# SCH_Namu_Board_v1_2023-11-06.net
KiCad netlist of a schematic drawn in EasyEDA
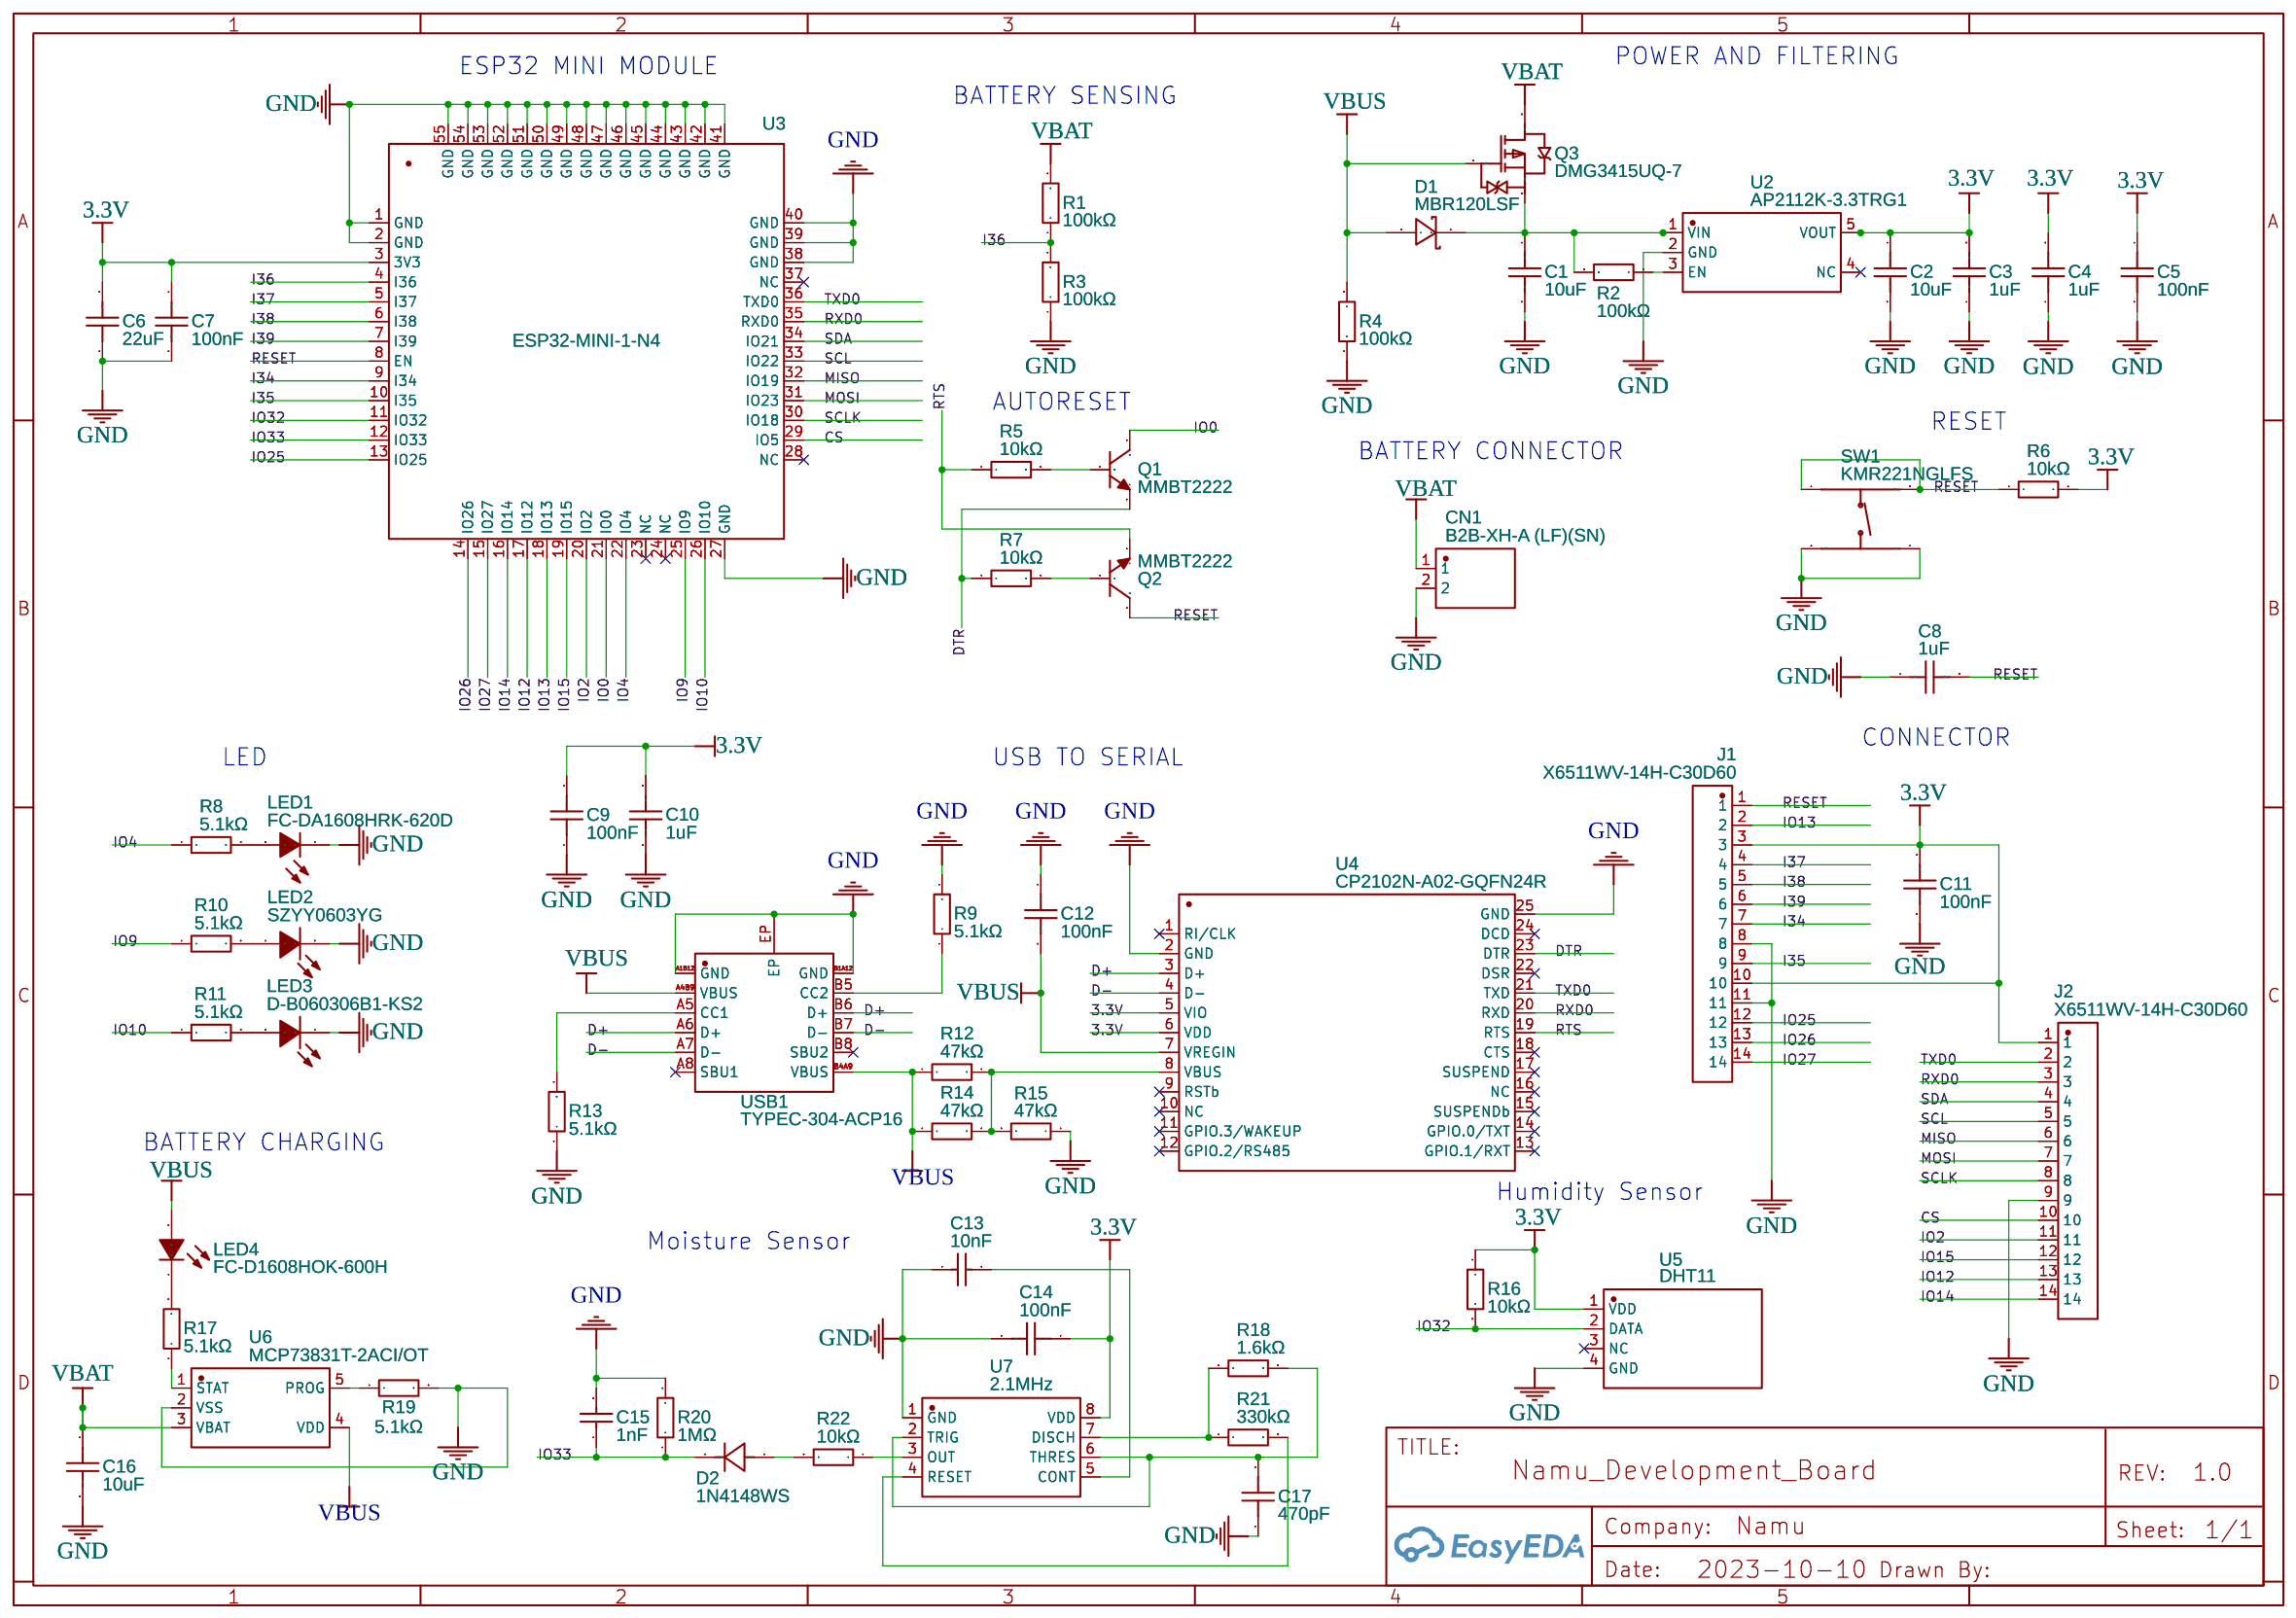
[diagram p0: schematic sheet]

(export (version "E")
  (design (tool "Eeschema 10.0.6"))
  (components
    (comp (ref "C1")
      (value "10uF")
      (fields
        (field (name "Manufacturer Part") "CS3216X7R106K250NRI")
        (field (name "Manufacturer") "SAMWHA(三和)")
      )
      (libsource (lib "") (part "CS3216X7R106K250NRI"))
    )
    (comp (ref "C2")
      (value "10uF")
      (fields
        (field (name "Manufacturer Part") "CS3216X7R106K250NRI")
        (field (name "Manufacturer") "SAMWHA(三和)")
      )
      (libsource (lib "") (part "CS3216X7R106K250NRI"))
    )
    (comp (ref "C3")
      (value "1uF")
      (fields
        (field (name "Manufacturer Part") "CS1608X7R105K250NRB")
        (field (name "Manufacturer") "SAMWHA(三和)")
      )
      (libsource (lib "") (part "CS1608X7R105K250NRB_1"))
    )
    (comp (ref "C4")
      (value "1uF")
      (fields
        (field (name "Manufacturer Part") "CS1608X7R105K250NRB")
        (field (name "Manufacturer") "SAMWHA(三和)")
      )
      (libsource (lib "") (part "CS1608X7R105K250NRB_1"))
    )
    (comp (ref "C5")
      (value "100nF")
      (fields (field (name "Manufacturer Part") "C1005X5R1C104KT000F") (field (name "Manufacturer") "TDK"))
      (libsource (lib "") (part "C1005X5R1C104KT000F"))
    )
    (comp (ref "C6")
      (value "22uF")
      (fields
        (field (name "Manufacturer Part") "CS3216X5R226K160NRI")
        (field (name "Manufacturer") "SAMWHA(三和)")
      )
      (libsource (lib "") (part "CS3216X5R226K160NRI"))
    )
    (comp (ref "C7")
      (value "100nF")
      (fields (field (name "Manufacturer Part") "C1005X5R1C104KT000F") (field (name "Manufacturer") "TDK"))
      (libsource (lib "") (part "C1005X5R1C104KT000F"))
    )
    (comp (ref "C8")
      (value "1uF")
      (fields
        (field (name "Manufacturer Part") "CS1608X7R105K250NRB")
        (field (name "Manufacturer") "SAMWHA(三和)")
      )
      (libsource (lib "") (part "CS1608X7R105K250NRB"))
    )
    (comp (ref "C9")
      (value "100nF")
      (fields (field (name "Manufacturer Part") "C1005X5R1C104KT000F") (field (name "Manufacturer") "TDK"))
      (libsource (lib "") (part "C1005X5R1C104KT000F_2"))
    )
    (comp (ref "C10")
      (value "1uF")
      (fields
        (field (name "Manufacturer Part") "CS1608X7R105K250NRB")
        (field (name "Manufacturer") "SAMWHA(三和)")
      )
      (libsource (lib "") (part "CS1608X7R105K250NRB_1"))
    )
    (comp (ref "C11")
      (value "100nF")
      (fields (field (name "Manufacturer Part") "C1005X5R1C104KT000F") (field (name "Manufacturer") "TDK"))
      (libsource (lib "") (part "C1005X5R1C104KT000F"))
    )
    (comp (ref "C12")
      (value "100nF")
      (fields (field (name "Manufacturer Part") "C1005X5R1C104KT000F") (field (name "Manufacturer") "TDK"))
      (libsource (lib "") (part "C1005X5R1C104KT000F"))
    )
    (comp (ref "C13")
      (value "10nF")
      (fields
        (field (name "Manufacturer Part") "CC0402KRX7R9BB103")
        (field (name "Manufacturer") "YAGEO(国巨)")
      )
      (libsource (lib "") (part "CC0402KRX7R9BB103"))
    )
    (comp (ref "C14")
      (value "100nF")
      (fields (field (name "Manufacturer Part") "C1005X5R1C104KT000F") (field (name "Manufacturer") "TDK"))
      (libsource (lib "") (part "C1005X5R1C104KT000F_1"))
    )
    (comp (ref "C15")
      (value "1nF")
      (fields
        (field (name "Manufacturer Part") "CC0402KRX7R9BB102")
        (field (name "Manufacturer") "YAGEO(国巨)")
      )
      (libsource (lib "") (part "CC0402KRX7R9BB102"))
    )
    (comp (ref "C16")
      (value "10uF")
      (fields
        (field (name "Manufacturer Part") "CS3216X7R106K250NRI")
        (field (name "Manufacturer") "SAMWHA(三和)")
      )
      (libsource (lib "") (part "CS3216X7R106K250NRI"))
    )
    (comp (ref "C17")
      (value "470pF")
      (fields
        (field (name "Manufacturer Part") "CC0402KRX7R9BB471")
        (field (name "Manufacturer") "YAGEO(国巨)")
      )
      (libsource (lib "") (part "CC0402KRX7R9BB471"))
    )
    (comp (ref "CN1")
      (value "B2B-XH-A (LF)(SN)")
      (fields (field (name "Manufacturer Part") "B2B-XH-A(LF)(SN)") (field (name "Manufacturer") "JST"))
      (libsource (lib "") (part "B2B-XH-A (LF)(SN)"))
    )
    (comp (ref "D1")
      (value "MBR120LSF")
      (fields (field (name "Manufacturer") "SHIKUES(时科)"))
      (libsource (lib "") (part "MBR120LSF"))
    )
    (comp (ref "D2")
      (value "1N4148WS")
      (fields (field (name "Manufacturer") "TWGMC(台湾迪嘉)"))
      (libsource (lib "") (part "1N4148WS_C727111"))
    )
    (comp (ref "J1")
      (value "X6511WV-14H-C30D60")
      (fields (field (name "Manufacturer") "XKB Connectivity(中国星坤)"))
      (libsource (lib "") (part "X6511WV-14H-C30D60"))
    )
    (comp (ref "J2")
      (value "X6511WV-14H-C30D60")
      (fields (field (name "Manufacturer") "XKB Connectivity(中国星坤)"))
      (libsource (lib "") (part "X6511WV-14H-C30D60_1"))
    )
    (comp (ref "LED1")
      (value "FC-DA1608HRK-620D")
      (fields (field (name "Manufacturer Part") "NCD0603R1") (field (name "Manufacturer") "国星光电"))
      (libsource (lib "") (part "FC-DA1608HRK-620D"))
    )
    (comp (ref "LED2")
      (value "SZYY0603YG")
      (fields (field (name "Manufacturer") "yongyu(永裕光电)"))
      (libsource (lib "") (part "SZYY0603YG"))
    )
    (comp (ref "LED3")
      (value "D-B060306B1-KS2")
      (fields (field (name "Manufacturer Part") "D-060306B1") (field (name "Manufacturer") "ARKLED(方舟)"))
      (libsource (lib "") (part "D-B060306B1-KS2"))
    )
    (comp (ref "LED4")
      (value "FC-D1608HOK-600H")
      (fields (field (name "Manufacturer Part") "NCD0603O1") (field (name "Manufacturer") "国星光电"))
      (libsource (lib "") (part "FC-D1608HOK-600H"))
    )
    (comp (ref "Q1")
      (value "MMBT2222")
      (fields (field (name "Manufacturer") "YONGYUTAI(永裕泰)"))
      (libsource (lib "") (part "MMBT2222_1"))
    )
    (comp (ref "Q2")
      (value "MMBT2222")
      (fields (field (name "Manufacturer") "YONGYUTAI(永裕泰)"))
      (libsource (lib "") (part "MMBT2222"))
    )
    (comp (ref "Q3")
      (value "DMG3415UQ-7")
      (fields (field (name "Manufacturer") "DIODES(美台)"))
      (libsource (lib "") (part "DMG3415UQ-7"))
    )
    (comp (ref "R1")
      (value "100kΩ")
      (fields
        (field (name "Manufacturer Part") "0603WAF1003T5E")
        (field (name "Manufacturer") "UNI-ROYAL(厚声)")
      )
      (libsource (lib "") (part "0603WAF1003T5E_1"))
    )
    (comp (ref "R2")
      (value "100kΩ")
      (fields
        (field (name "Manufacturer Part") "0603WAF1003T5E")
        (field (name "Manufacturer") "UNI-ROYAL(厚声)")
      )
      (libsource (lib "") (part "0603WAF1003T5E"))
    )
    (comp (ref "R3")
      (value "100kΩ")
      (fields
        (field (name "Manufacturer Part") "0603WAF1003T5E")
        (field (name "Manufacturer") "UNI-ROYAL(厚声)")
      )
      (libsource (lib "") (part "0603WAF1003T5E_1"))
    )
    (comp (ref "R4")
      (value "100kΩ")
      (fields
        (field (name "Manufacturer Part") "0603WAF1003T5E")
        (field (name "Manufacturer") "UNI-ROYAL(厚声)")
      )
      (libsource (lib "") (part "0603WAF1003T5E_1"))
    )
    (comp (ref "R5")
      (value "10kΩ")
      (fields (field (name "Manufacturer Part") "RC0603FR-0710KL") (field (name "Manufacturer") "YAGEO(国巨)"))
      (libsource (lib "") (part "RC0603FR-0710KL"))
    )
    (comp (ref "R6")
      (value "10kΩ")
      (fields (field (name "Manufacturer Part") "RC0603FR-0710KL") (field (name "Manufacturer") "YAGEO(国巨)"))
      (libsource (lib "") (part "RC0603FR-0710KL"))
    )
    (comp (ref "R7")
      (value "10kΩ")
      (fields (field (name "Manufacturer Part") "RC0603FR-0710KL") (field (name "Manufacturer") "YAGEO(国巨)"))
      (libsource (lib "") (part "RC0603FR-0710KL"))
    )
    (comp (ref "R8")
      (value "5.1kΩ")
      (fields (field (name "Manufacturer Part") "RMC04025.1K5%N") (field (name "Manufacturer") "Tyohm(幸亚电阻)"))
      (libsource (lib "") (part "RMC04025.1K5%N_1"))
    )
    (comp (ref "R9")
      (value "5.1kΩ")
      (fields (field (name "Manufacturer Part") "RMC04025.1K5%N") (field (name "Manufacturer") "Tyohm(幸亚电阻)"))
      (libsource (lib "") (part "RMC04025.1K5%N"))
    )
    (comp (ref "R10")
      (value "5.1kΩ")
      (fields (field (name "Manufacturer Part") "RMC04025.1K5%N") (field (name "Manufacturer") "Tyohm(幸亚电阻)"))
      (libsource (lib "") (part "RMC04025.1K5%N_1"))
    )
    (comp (ref "R11")
      (value "5.1kΩ")
      (fields (field (name "Manufacturer Part") "RMC04025.1K5%N") (field (name "Manufacturer") "Tyohm(幸亚电阻)"))
      (libsource (lib "") (part "RMC04025.1K5%N_1"))
    )
    (comp (ref "R12")
      (value "47kΩ")
      (fields
        (field (name "Manufacturer Part") "0402WGF4702TCE")
        (field (name "Manufacturer") "UNI-ROYAL(厚声)")
      )
      (libsource (lib "") (part "0402WGF4702TCE_1"))
    )
    (comp (ref "R13")
      (value "5.1kΩ")
      (fields (field (name "Manufacturer Part") "RMC04025.1K5%N") (field (name "Manufacturer") "Tyohm(幸亚电阻)"))
      (libsource (lib "") (part "RMC04025.1K5%N"))
    )
    (comp (ref "R14")
      (value "47kΩ")
      (fields
        (field (name "Manufacturer Part") "0402WGF4702TCE")
        (field (name "Manufacturer") "UNI-ROYAL(厚声)")
      )
      (libsource (lib "") (part "0402WGF4702TCE_1"))
    )
    (comp (ref "R15")
      (value "47kΩ")
      (fields
        (field (name "Manufacturer Part") "0402WGF4702TCE")
        (field (name "Manufacturer") "UNI-ROYAL(厚声)")
      )
      (libsource (lib "") (part "0402WGF4702TCE"))
    )
    (comp (ref "R16")
      (value "10kΩ")
      (fields (field (name "Manufacturer Part") "RC0603FR-0710KL") (field (name "Manufacturer") "YAGEO(国巨)"))
      (libsource (lib "") (part "RC0603FR-0710KL_2"))
    )
    (comp (ref "R17")
      (value "5.1kΩ")
      (fields (field (name "Manufacturer Part") "RMC04025.1K5%N") (field (name "Manufacturer") "Tyohm(幸亚电阻)"))
      (libsource (lib "") (part "RMC04025.1K5%N"))
    )
    (comp (ref "R18")
      (value "1.6kΩ")
      (fields
        (field (name "Manufacturer Part") "0402WGF1601TCE")
        (field (name "Manufacturer") "UNI-ROYAL(厚声)")
      )
      (libsource (lib "") (part "0402WGF1601TCE"))
    )
    (comp (ref "R19")
      (value "5.1kΩ")
      (fields (field (name "Manufacturer Part") "RMC04025.1K5%N") (field (name "Manufacturer") "Tyohm(幸亚电阻)"))
      (libsource (lib "") (part "RMC04025.1K5%N_1"))
    )
    (comp (ref "R20")
      (value "1MΩ")
      (fields
        (field (name "Manufacturer Part") "0402WGF1004TCE")
        (field (name "Manufacturer") "UNI-ROYAL(厚声)")
      )
      (libsource (lib "") (part "0402WGF1004TCE"))
    )
    (comp (ref "R21")
      (value "330kΩ")
      (fields
        (field (name "Manufacturer Part") "0402WGF3303TCE")
        (field (name "Manufacturer") "UNI-ROYAL(厚声)")
      )
      (libsource (lib "") (part "0402WGF3303TCE"))
    )
    (comp (ref "R22")
      (value "10kΩ")
      (fields (field (name "Manufacturer Part") "RC0603FR-0710KL") (field (name "Manufacturer") "YAGEO(国巨)"))
      (libsource (lib "") (part "RC0603FR-0710KL_1"))
    )
    (comp (ref "SW1")
      (value "KMR221NGLFS")
      (fields (field (name "Manufacturer") "C&K"))
      (libsource (lib "") (part "KMR221NGLFS"))
    )
    (comp (ref "U2")
      (value "AP2112K-3.3TRG1")
      (fields (field (name "Manufacturer") "DIODES(美台)"))
      (libsource (lib "") (part "AP2112K-3.3TRG1"))
    )
    (comp (ref "U3")
      (value "ESP32-MINI-1-N4")
      (fields (field (name "Manufacturer") "ESPRESSIF(乐鑫)"))
      (libsource (lib "") (part "ESP32-MINI-1-N4"))
    )
    (comp (ref "U4")
      (value "CP2102N-A02-GQFN24R")
      (fields (field (name "Manufacturer") "SILICON LABS(芯科)"))
      (libsource (lib "") (part "CP2102N-A02-GQFN24R"))
    )
    (comp (ref "U5")
      (value "DHT11")
      (fields (field (name "Manufacturer") "广州奥松"))
      (libsource (lib "") (part "DHT11"))
    )
    (comp (ref "U6")
      (value "MCP73831T-2ACI/OT")
      (fields (field (name "Manufacturer") "MICROCHIP(美国微芯)"))
      (libsource (lib "") (part "MCP73831T-2ACI/OT"))
    )
    (comp (ref "U7")
      (value "2.1MHz")
      (fields (field (name "Manufacturer Part") "TLC555IDR") (field (name "Manufacturer") "TI(德州仪器)"))
      (libsource (lib "") (part "TLC555IDR"))
    )
    (comp (ref "USB1")
      (value "TYPEC-304-ACP16")
      (fields (field (name "Manufacturer") "XUNPU(讯普)"))
      (libsource (lib "") (part "TYPEC-304-ACP16"))
    )
  )
  (nets
    (net (code "1") (name "/CS") (class "Default")
      (node (ref "J2") (pin "10") (pinfunction "10_10") (pintype "unspecified"))
      (node (ref "U3") (pin "29") (pinfunction "IO5_29") (pintype "unspecified"))
    )
    (net (code "2") (name "/D+") (class "Default")
      (node (ref "U4") (pin "3") (pinfunction "D+_3") (pintype "unspecified"))
      (node (ref "USB1") (pin "A6") (pinfunction "D+_A6") (pintype "unspecified"))
      (node (ref "USB1") (pin "B6") (pinfunction "D+_B6") (pintype "unspecified"))
    )
    (net (code "3") (name "/D-") (class "Default")
      (node (ref "U4") (pin "4") (pinfunction "D-_4") (pintype "unspecified"))
      (node (ref "USB1") (pin "A7") (pinfunction "D-_A7") (pintype "unspecified"))
      (node (ref "USB1") (pin "B7") (pinfunction "D-_B7") (pintype "unspecified"))
    )
    (net (code "4") (name "/DTR") (class "Default")
      (node (ref "Q1") (pin "2") (pinfunction "E_2") (pintype "input"))
      (node (ref "R7") (pin "1") (pinfunction "1_1") (pintype "input"))
      (node (ref "U4") (pin "23") (pinfunction "DTR_23") (pintype "unspecified"))
    )
    (net (code "5") (name "/I34") (class "Default")
      (node (ref "J1") (pin "7") (pinfunction "7_7") (pintype "unspecified"))
      (node (ref "U3") (pin "9") (pinfunction "I34_9") (pintype "unspecified"))
    )
    (net (code "6") (name "/I35") (class "Default")
      (node (ref "J1") (pin "9") (pinfunction "9_9") (pintype "unspecified"))
      (node (ref "U3") (pin "10") (pinfunction "I35_10") (pintype "unspecified"))
    )
    (net (code "7") (name "/I36") (class "Default")
      (node (ref "R1") (pin "1") (pinfunction "1_1") (pintype "input"))
      (node (ref "R3") (pin "2") (pinfunction "2_2") (pintype "input"))
      (node (ref "U3") (pin "4") (pinfunction "I36_4") (pintype "unspecified"))
    )
    (net (code "8") (name "/I37") (class "Default")
      (node (ref "J1") (pin "4") (pinfunction "4_4") (pintype "unspecified"))
      (node (ref "U3") (pin "5") (pinfunction "I37_5") (pintype "unspecified"))
    )
    (net (code "9") (name "/I38") (class "Default")
      (node (ref "J1") (pin "5") (pinfunction "5_5") (pintype "unspecified"))
      (node (ref "U3") (pin "6") (pinfunction "I38_6") (pintype "unspecified"))
    )
    (net (code "10") (name "/I39") (class "Default")
      (node (ref "J1") (pin "6") (pinfunction "6_6") (pintype "unspecified"))
      (node (ref "U3") (pin "7") (pinfunction "I39_7") (pintype "unspecified"))
    )
    (net (code "11") (name "/IO0") (class "Default")
      (node (ref "Q1") (pin "3") (pinfunction "C_3") (pintype "input"))
      (node (ref "U3") (pin "21") (pinfunction "IO0_21") (pintype "unspecified"))
    )
    (net (code "12") (name "/IO2") (class "Default")
      (node (ref "J2") (pin "11") (pinfunction "11_11") (pintype "unspecified"))
      (node (ref "U3") (pin "20") (pinfunction "IO2_20") (pintype "unspecified"))
    )
    (net (code "13") (name "/IO4") (class "Default")
      (node (ref "R8") (pin "1") (pinfunction "1_1") (pintype "unspecified"))
      (node (ref "U3") (pin "22") (pinfunction "IO4_22") (pintype "unspecified"))
    )
    (net (code "14") (name "/IO9") (class "Default")
      (node (ref "R10") (pin "1") (pinfunction "1_1") (pintype "unspecified"))
      (node (ref "U3") (pin "25") (pinfunction "IO9_25") (pintype "unspecified"))
    )
    (net (code "15") (name "/IO10") (class "Default")
      (node (ref "R11") (pin "1") (pinfunction "1_1") (pintype "unspecified"))
      (node (ref "U3") (pin "26") (pinfunction "IO10_26") (pintype "unspecified"))
    )
    (net (code "16") (name "/IO12") (class "Default")
      (node (ref "J2") (pin "13") (pinfunction "13_13") (pintype "unspecified"))
      (node (ref "U3") (pin "17") (pinfunction "IO12_17") (pintype "unspecified"))
    )
    (net (code "17") (name "/IO13") (class "Default")
      (node (ref "J1") (pin "2") (pinfunction "2_2") (pintype "unspecified"))
      (node (ref "U3") (pin "18") (pinfunction "IO13_18") (pintype "unspecified"))
    )
    (net (code "18") (name "/IO14") (class "Default")
      (node (ref "J2") (pin "14") (pinfunction "14_14") (pintype "unspecified"))
      (node (ref "U3") (pin "16") (pinfunction "IO14_16") (pintype "unspecified"))
    )
    (net (code "19") (name "/IO15") (class "Default")
      (node (ref "J2") (pin "12") (pinfunction "12_12") (pintype "unspecified"))
      (node (ref "U3") (pin "19") (pinfunction "IO15_19") (pintype "unspecified"))
    )
    (net (code "20") (name "/IO25") (class "Default")
      (node (ref "J1") (pin "12") (pinfunction "12_12") (pintype "unspecified"))
      (node (ref "U3") (pin "13") (pinfunction "IO25_13") (pintype "unspecified"))
    )
    (net (code "21") (name "/IO26") (class "Default")
      (node (ref "J1") (pin "13") (pinfunction "13_13") (pintype "unspecified"))
      (node (ref "U3") (pin "14") (pinfunction "IO26_14") (pintype "unspecified"))
    )
    (net (code "22") (name "/IO27") (class "Default")
      (node (ref "J1") (pin "14") (pinfunction "14_14") (pintype "unspecified"))
      (node (ref "U3") (pin "15") (pinfunction "IO27_15") (pintype "unspecified"))
    )
    (net (code "23") (name "/IO32") (class "Default")
      (node (ref "R16") (pin "2") (pinfunction "2_2") (pintype "input"))
      (node (ref "U3") (pin "11") (pinfunction "IO32_11") (pintype "unspecified"))
      (node (ref "U5") (pin "2") (pinfunction "DATA_2") (pintype "unspecified"))
    )
    (net (code "24") (name "/IO33") (class "Default")
      (node (ref "C15") (pin "1") (pinfunction "1_1") (pintype "input"))
      (node (ref "D2") (pin "1") (pinfunction "C_1") (pintype "unspecified"))
      (node (ref "R20") (pin "1") (pinfunction "1_1") (pintype "input"))
      (node (ref "U3") (pin "12") (pinfunction "IO33_12") (pintype "unspecified"))
    )
    (net (code "25") (name "/MISO") (class "Default")
      (node (ref "J2") (pin "6") (pinfunction "6_6") (pintype "unspecified"))
      (node (ref "U3") (pin "32") (pinfunction "IO19_32") (pintype "unspecified"))
    )
    (net (code "26") (name "/MOSI") (class "Default")
      (node (ref "J2") (pin "7") (pinfunction "7_7") (pintype "unspecified"))
      (node (ref "U3") (pin "31") (pinfunction "IO23_31") (pintype "unspecified"))
    )
    (net (code "27") (name "/RESET") (class "Default")
      (node (ref "C8") (pin "2") (pinfunction "2_2") (pintype "unspecified"))
      (node (ref "J1") (pin "1") (pinfunction "1_1") (pintype "unspecified"))
      (node (ref "Q2") (pin "3") (pinfunction "C_3") (pintype "input"))
      (node (ref "R6") (pin "1") (pinfunction "1_1") (pintype "input"))
      (node (ref "SW1") (pin "1") (pinfunction "1_1") (pintype "input"))
      (node (ref "SW1") (pin "2") (pinfunction "2_2") (pintype "input"))
      (node (ref "U3") (pin "8") (pinfunction "EN_8") (pintype "unspecified"))
    )
    (net (code "28") (name "/RTS") (class "Default")
      (node (ref "Q2") (pin "2") (pinfunction "E_2") (pintype "input"))
      (node (ref "R5") (pin "1") (pinfunction "1_1") (pintype "input"))
      (node (ref "U4") (pin "19") (pinfunction "RTS_19") (pintype "unspecified"))
    )
    (net (code "29") (name "/RXD0") (class "Default")
      (node (ref "J2") (pin "3") (pinfunction "3_3") (pintype "unspecified"))
      (node (ref "U3") (pin "35") (pinfunction "RXD0_35") (pintype "unspecified"))
      (node (ref "U4") (pin "20") (pinfunction "RXD_20") (pintype "unspecified"))
    )
    (net (code "30") (name "/SCL") (class "Default")
      (node (ref "J2") (pin "5") (pinfunction "5_5") (pintype "unspecified"))
      (node (ref "U3") (pin "33") (pinfunction "IO22_33") (pintype "unspecified"))
    )
    (net (code "31") (name "/SCLK") (class "Default")
      (node (ref "J2") (pin "8") (pinfunction "8_8") (pintype "unspecified"))
      (node (ref "U3") (pin "30") (pinfunction "IO18_30") (pintype "unspecified"))
    )
    (net (code "32") (name "/SDA") (class "Default")
      (node (ref "J2") (pin "4") (pinfunction "4_4") (pintype "unspecified"))
      (node (ref "U3") (pin "34") (pinfunction "IO21_34") (pintype "unspecified"))
    )
    (net (code "33") (name "/TXD0") (class "Default")
      (node (ref "J2") (pin "2") (pinfunction "2_2") (pintype "unspecified"))
      (node (ref "U3") (pin "36") (pinfunction "TXD0_36") (pintype "unspecified"))
      (node (ref "U4") (pin "21") (pinfunction "TXD_21") (pintype "unspecified"))
    )
    (net (code "34") (name "3.3V") (class "Default")
      (node (ref "C10") (pin "2") (pinfunction "2_2") (pintype "unspecified"))
      (node (ref "C11") (pin "1") (pinfunction "1_1") (pintype "unspecified"))
      (node (ref "C14") (pin "1") (pinfunction "1_1") (pintype "unspecified"))
      (node (ref "C2") (pin "1") (pinfunction "1_1") (pintype "unspecified"))
      (node (ref "C3") (pin "2") (pinfunction "2_2") (pintype "unspecified"))
      (node (ref "C4") (pin "2") (pinfunction "2_2") (pintype "unspecified"))
      (node (ref "C5") (pin "1") (pinfunction "1_1") (pintype "unspecified"))
      (node (ref "C6") (pin "2") (pinfunction "2_2") (pintype "unspecified"))
      (node (ref "C7") (pin "1") (pinfunction "1_1") (pintype "unspecified"))
      (node (ref "C9") (pin "2") (pinfunction "2_2") (pintype "unspecified"))
      (node (ref "J1") (pin "10") (pinfunction "10_10") (pintype "unspecified"))
      (node (ref "J1") (pin "3") (pinfunction "3_3") (pintype "unspecified"))
      (node (ref "J2") (pin "1") (pinfunction "1_1") (pintype "unspecified"))
      (node (ref "R16") (pin "1") (pinfunction "1_1") (pintype "input"))
      (node (ref "R6") (pin "2") (pinfunction "2_2") (pintype "input"))
      (node (ref "U2") (pin "5") (pinfunction "VOUT_5") (pintype "unspecified"))
      (node (ref "U3") (pin "3") (pinfunction "3V3_3") (pintype "unspecified"))
      (node (ref "U4") (pin "5") (pinfunction "VIO_5") (pintype "unspecified"))
      (node (ref "U4") (pin "6") (pinfunction "VDD_6") (pintype "unspecified"))
      (node (ref "U5") (pin "1") (pinfunction "VDD_1") (pintype "unspecified"))
      (node (ref "U7") (pin "8") (pinfunction "VDD_8") (pintype "unspecified"))
    )
    (net (code "35") (name "GND") (class "Default")
      (node (ref "C1") (pin "2") (pinfunction "2_2") (pintype "unspecified"))
      (node (ref "C10") (pin "1") (pinfunction "1_1") (pintype "unspecified"))
      (node (ref "C11") (pin "2") (pinfunction "2_2") (pintype "unspecified"))
      (node (ref "C12") (pin "1") (pinfunction "1_1") (pintype "unspecified"))
      (node (ref "C13") (pin "1") (pinfunction "1_1") (pintype "input"))
      (node (ref "C14") (pin "2") (pinfunction "2_2") (pintype "unspecified"))
      (node (ref "C15") (pin "2") (pinfunction "2_2") (pintype "input"))
      (node (ref "C16") (pin "2") (pinfunction "2_2") (pintype "unspecified"))
      (node (ref "C17") (pin "1") (pinfunction "1_1") (pintype "unspecified"))
      (node (ref "C2") (pin "2") (pinfunction "2_2") (pintype "unspecified"))
      (node (ref "C3") (pin "1") (pinfunction "1_1") (pintype "unspecified"))
      (node (ref "C4") (pin "1") (pinfunction "1_1") (pintype "unspecified"))
      (node (ref "C5") (pin "2") (pinfunction "2_2") (pintype "unspecified"))
      (node (ref "C6") (pin "1") (pinfunction "1_1") (pintype "unspecified"))
      (node (ref "C7") (pin "2") (pinfunction "2_2") (pintype "unspecified"))
      (node (ref "C8") (pin "1") (pinfunction "1_1") (pintype "unspecified"))
      (node (ref "C9") (pin "1") (pinfunction "1_1") (pintype "unspecified"))
      (node (ref "CN1") (pin "2") (pinfunction "2_2") (pintype "unspecified"))
      (node (ref "J1") (pin "11") (pinfunction "11_11") (pintype "unspecified"))
      (node (ref "J1") (pin "8") (pinfunction "8_8") (pintype "unspecified"))
      (node (ref "J2") (pin "9") (pinfunction "9_9") (pintype "unspecified"))
      (node (ref "LED1") (pin "1") (pinfunction "K_1") (pintype "input"))
      (node (ref "LED2") (pin "2") (pinfunction "-_2") (pintype "unspecified"))
      (node (ref "LED3") (pin "1") (pinfunction "1_1") (pintype "unspecified"))
      (node (ref "R13") (pin "1") (pinfunction "1_1") (pintype "unspecified"))
      (node (ref "R15") (pin "1") (pinfunction "1_1") (pintype "input"))
      (node (ref "R19") (pin "2") (pinfunction "2_2") (pintype "unspecified"))
      (node (ref "R20") (pin "2") (pinfunction "2_2") (pintype "input"))
      (node (ref "R3") (pin "1") (pinfunction "1_1") (pintype "input"))
      (node (ref "R4") (pin "1") (pinfunction "1_1") (pintype "input"))
      (node (ref "R9") (pin "2") (pinfunction "2_2") (pintype "unspecified"))
      (node (ref "SW1") (pin "3") (pinfunction "3_3") (pintype "input"))
      (node (ref "SW1") (pin "4") (pinfunction "4_4") (pintype "input"))
      (node (ref "U2") (pin "2") (pinfunction "GND_2") (pintype "unspecified"))
      (node (ref "U3") (pin "1") (pinfunction "GND_1") (pintype "unspecified"))
      (node (ref "U3") (pin "2") (pinfunction "GND_2") (pintype "unspecified"))
      (node (ref "U3") (pin "27") (pinfunction "GND_27") (pintype "unspecified"))
      (node (ref "U3") (pin "38") (pinfunction "GND_38") (pintype "unspecified"))
      (node (ref "U3") (pin "39") (pinfunction "GND_39") (pintype "unspecified"))
      (node (ref "U3") (pin "40") (pinfunction "GND_40") (pintype "unspecified"))
      (node (ref "U3") (pin "41") (pinfunction "GND_41") (pintype "unspecified"))
      (node (ref "U3") (pin "42") (pinfunction "GND_42") (pintype "unspecified"))
      (node (ref "U3") (pin "43") (pinfunction "GND_43") (pintype "unspecified"))
      (node (ref "U3") (pin "44") (pinfunction "GND_44") (pintype "unspecified"))
      (node (ref "U3") (pin "45") (pinfunction "GND_45") (pintype "unspecified"))
      (node (ref "U3") (pin "46") (pinfunction "GND_46") (pintype "unspecified"))
      (node (ref "U3") (pin "47") (pinfunction "GND_47") (pintype "unspecified"))
      (node (ref "U3") (pin "48") (pinfunction "GND_48") (pintype "unspecified"))
      (node (ref "U3") (pin "49") (pinfunction "GND_49") (pintype "unspecified"))
      (node (ref "U3") (pin "50") (pinfunction "GND_50") (pintype "unspecified"))
      (node (ref "U3") (pin "51") (pinfunction "GND_51") (pintype "unspecified"))
      (node (ref "U3") (pin "52") (pinfunction "GND_52") (pintype "unspecified"))
      (node (ref "U3") (pin "53") (pinfunction "GND_53") (pintype "unspecified"))
      (node (ref "U3") (pin "54") (pinfunction "GND_54") (pintype "unspecified"))
      (node (ref "U3") (pin "55") (pinfunction "GND_55") (pintype "unspecified"))
      (node (ref "U4") (pin "2") (pinfunction "GND_2") (pintype "unspecified"))
      (node (ref "U4") (pin "25") (pinfunction "GND_25") (pintype "unspecified"))
      (node (ref "U5") (pin "4") (pinfunction "GND_4") (pintype "unspecified"))
      (node (ref "U6") (pin "2") (pinfunction "VSS_2") (pintype "unspecified"))
      (node (ref "U7") (pin "1") (pinfunction "GND_1") (pintype "unspecified"))
      (node (ref "USB1") (pin "A1B12") (pinfunction "GND_A1B12") (pintype "unspecified"))
      (node (ref "USB1") (pin "B1A12") (pinfunction "GND_B1A12") (pintype "unspecified"))
      (node (ref "USB1") (pin "EP") (pinfunction "EP_EP") (pintype "unspecified"))
    )
    (net (code "36") (name "Net-(D1-C)") (class "Default")
      (node (ref "C1") (pin "1") (pinfunction "1_1") (pintype "unspecified"))
      (node (ref "D1") (pin "1") (pinfunction "C_1") (pintype "unspecified"))
      (node (ref "Q3") (pin "2") (pinfunction "S_2") (pintype "unspecified"))
      (node (ref "R2") (pin "2") (pinfunction "2_2") (pintype "input"))
      (node (ref "U2") (pin "1") (pinfunction "VIN_1") (pintype "unspecified"))
    )
    (net (code "37") (name "Net-(D2-A)") (class "Default")
      (node (ref "D2") (pin "2") (pinfunction "A_2") (pintype "unspecified"))
      (node (ref "R22") (pin "2") (pinfunction "2_2") (pintype "input"))
    )
    (net (code "38") (name "Net-(LED1-A)") (class "Default")
      (node (ref "LED1") (pin "2") (pinfunction "A_2") (pintype "input"))
      (node (ref "R8") (pin "2") (pinfunction "2_2") (pintype "unspecified"))
    )
    (net (code "39") (name "Net-(LED2-+)") (class "Default")
      (node (ref "LED2") (pin "1") (pinfunction "+_1") (pintype "unspecified"))
      (node (ref "R10") (pin "2") (pinfunction "2_2") (pintype "unspecified"))
    )
    (net (code "40") (name "Net-(LED3-Pad2)") (class "Default")
      (node (ref "LED3") (pin "2") (pinfunction "2_2") (pintype "unspecified"))
      (node (ref "R11") (pin "2") (pinfunction "2_2") (pintype "unspecified"))
    )
    (net (code "41") (name "Net-(LED4-K)") (class "Default")
      (node (ref "LED4") (pin "1") (pinfunction "K_1") (pintype "input"))
      (node (ref "R17") (pin "2") (pinfunction "2_2") (pintype "unspecified"))
    )
    (net (code "42") (name "Net-(Q1-B)") (class "Default")
      (node (ref "Q1") (pin "1") (pinfunction "B_1") (pintype "input"))
      (node (ref "R5") (pin "2") (pinfunction "2_2") (pintype "input"))
    )
    (net (code "43") (name "Net-(Q2-B)") (class "Default")
      (node (ref "Q2") (pin "1") (pinfunction "B_1") (pintype "input"))
      (node (ref "R7") (pin "2") (pinfunction "2_2") (pintype "input"))
    )
    (net (code "44") (name "Net-(U2-EN)") (class "Default")
      (node (ref "R2") (pin "1") (pinfunction "1_1") (pintype "input"))
      (node (ref "U2") (pin "3") (pinfunction "EN_3") (pintype "unspecified"))
    )
    (net (code "45") (name "Net-(U4-VBUS)") (class "Default")
      (node (ref "R12") (pin "2") (pinfunction "2_2") (pintype "input"))
      (node (ref "R14") (pin "2") (pinfunction "2_2") (pintype "input"))
      (node (ref "R15") (pin "2") (pinfunction "2_2") (pintype "input"))
      (node (ref "U4") (pin "8") (pinfunction "VBUS_8") (pintype "unspecified"))
    )
    (net (code "46") (name "Net-(U6-PROG)") (class "Default")
      (node (ref "R19") (pin "1") (pinfunction "1_1") (pintype "unspecified"))
      (node (ref "U6") (pin "5") (pinfunction "PROG_5") (pintype "unspecified"))
    )
    (net (code "47") (name "Net-(U6-STAT)") (class "Default")
      (node (ref "R17") (pin "1") (pinfunction "1_1") (pintype "unspecified"))
      (node (ref "U6") (pin "1") (pinfunction "STAT_1") (pintype "unspecified"))
    )
    (net (code "48") (name "Net-(U7-CONT)") (class "Default")
      (node (ref "C13") (pin "2") (pinfunction "2_2") (pintype "input"))
      (node (ref "U7") (pin "5") (pinfunction "CONT_5") (pintype "unspecified"))
    )
    (net (code "49") (name "Net-(U7-DISCH)") (class "Default")
      (node (ref "R18") (pin "1") (pinfunction "1_1") (pintype "input"))
      (node (ref "R21") (pin "1") (pinfunction "1_1") (pintype "input"))
      (node (ref "U7") (pin "7") (pinfunction "DISCH_7") (pintype "unspecified"))
    )
    (net (code "50") (name "Net-(U7-OUT)") (class "Default")
      (node (ref "R22") (pin "1") (pinfunction "1_1") (pintype "input"))
      (node (ref "U7") (pin "3") (pinfunction "OUT_3") (pintype "unspecified"))
    )
    (net (code "51") (name "Net-(U7-RESET)") (class "Default")
      (node (ref "R21") (pin "2") (pinfunction "2_2") (pintype "input"))
      (node (ref "U7") (pin "4") (pinfunction "RESET_4") (pintype "unspecified"))
    )
    (net (code "52") (name "Net-(U7-THRES)") (class "Default")
      (node (ref "C17") (pin "2") (pinfunction "2_2") (pintype "unspecified"))
      (node (ref "R18") (pin "2") (pinfunction "2_2") (pintype "input"))
      (node (ref "U7") (pin "2") (pinfunction "TRIG_2") (pintype "unspecified"))
      (node (ref "U7") (pin "6") (pinfunction "THRES_6") (pintype "unspecified"))
    )
    (net (code "53") (name "Net-(USB1-CC1)") (class "Default")
      (node (ref "R13") (pin "2") (pinfunction "2_2") (pintype "unspecified"))
      (node (ref "USB1") (pin "A5") (pinfunction "CC1_A5") (pintype "unspecified"))
    )
    (net (code "54") (name "Net-(USB1-CC2)") (class "Default")
      (node (ref "R9") (pin "1") (pinfunction "1_1") (pintype "unspecified"))
      (node (ref "USB1") (pin "B5") (pinfunction "CC2_B5") (pintype "unspecified"))
    )
    (net (code "55") (name "VBAT") (class "Default")
      (node (ref "C16") (pin "1") (pinfunction "1_1") (pintype "unspecified"))
      (node (ref "CN1") (pin "1") (pinfunction "1_1") (pintype "unspecified"))
      (node (ref "Q3") (pin "3") (pinfunction "D_3") (pintype "unspecified"))
      (node (ref "R1") (pin "2") (pinfunction "2_2") (pintype "input"))
      (node (ref "U6") (pin "3") (pinfunction "VBAT_3") (pintype "unspecified"))
    )
    (net (code "56") (name "VBUS") (class "Default")
      (node (ref "C12") (pin "2") (pinfunction "2_2") (pintype "unspecified"))
      (node (ref "D1") (pin "2") (pinfunction "A_2") (pintype "unspecified"))
      (node (ref "LED4") (pin "2") (pinfunction "A_2") (pintype "input"))
      (node (ref "Q3") (pin "1") (pinfunction "G_1") (pintype "unspecified"))
      (node (ref "R12") (pin "1") (pinfunction "1_1") (pintype "input"))
      (node (ref "R14") (pin "1") (pinfunction "1_1") (pintype "input"))
      (node (ref "R4") (pin "2") (pinfunction "2_2") (pintype "input"))
      (node (ref "U4") (pin "7") (pinfunction "VREGIN_7") (pintype "unspecified"))
      (node (ref "U6") (pin "4") (pinfunction "VDD_4") (pintype "unspecified"))
      (node (ref "USB1") (pin "A4B9") (pinfunction "VBUS_A4B9") (pintype "unspecified"))
      (node (ref "USB1") (pin "B4A9") (pinfunction "VBUS_B4A9") (pintype "unspecified"))
    )
    (net (code "57") (name "unconnected-(U2-NC-Pad4)") (class "Default")
      (node (ref "U2") (pin "4") (pinfunction "NC_4") (pintype "unspecified+no_connect"))
    )
    (net (code "58") (name "unconnected-(U3-NC-Pad23)") (class "Default")
      (node (ref "U3") (pin "23") (pinfunction "NC_23") (pintype "unspecified+no_connect"))
    )
    (net (code "59") (name "unconnected-(U3-NC-Pad24)") (class "Default")
      (node (ref "U3") (pin "24") (pinfunction "NC_24") (pintype "unspecified+no_connect"))
    )
    (net (code "60") (name "unconnected-(U3-NC-Pad28)") (class "Default")
      (node (ref "U3") (pin "28") (pinfunction "NC_28") (pintype "unspecified+no_connect"))
    )
    (net (code "61") (name "unconnected-(U3-NC-Pad37)") (class "Default")
      (node (ref "U3") (pin "37") (pinfunction "NC_37") (pintype "unspecified+no_connect"))
    )
    (net (code "62") (name "unconnected-(U4-CTS-Pad18)") (class "Default")
      (node (ref "U4") (pin "18") (pinfunction "CTS_18") (pintype "unspecified+no_connect"))
    )
    (net (code "63") (name "unconnected-(U4-DCD-Pad24)") (class "Default")
      (node (ref "U4") (pin "24") (pinfunction "DCD_24") (pintype "unspecified+no_connect"))
    )
    (net (code "64") (name "unconnected-(U4-DSR-Pad22)") (class "Default")
      (node (ref "U4") (pin "22") (pinfunction "DSR_22") (pintype "unspecified+no_connect"))
    )
    (net (code "65") (name "unconnected-(U4-GPIO.0{slash}TXT-Pad14)") (class "Default")
      (node (ref "U4") (pin "14") (pinfunction "GPIO.0/TXT_14") (pintype "unspecified+no_connect"))
    )
    (net (code "66") (name "unconnected-(U4-GPIO.1{slash}RXT-Pad13)") (class "Default")
      (node (ref "U4") (pin "13") (pinfunction "GPIO.1/RXT_13") (pintype "unspecified+no_connect"))
    )
    (net (code "67") (name "unconnected-(U4-GPIO.2{slash}RS485-Pad12)") (class "Default")
      (node (ref "U4") (pin "12") (pinfunction "GPIO.2/RS485_12") (pintype "unspecified+no_connect"))
    )
    (net (code "68") (name "unconnected-(U4-GPIO.3{slash}WAKEUP-Pad11)") (class "Default")
      (node (ref "U4") (pin "11") (pinfunction "GPIO.3/WAKEUP_11") (pintype "unspecified+no_connect"))
    )
    (net (code "69") (name "unconnected-(U4-NC-Pad10)") (class "Default")
      (node (ref "U4") (pin "10") (pinfunction "NC_10") (pintype "unspecified+no_connect"))
    )
    (net (code "70") (name "unconnected-(U4-NC-Pad16)") (class "Default")
      (node (ref "U4") (pin "16") (pinfunction "NC_16") (pintype "unspecified+no_connect"))
    )
    (net (code "71") (name "unconnected-(U4-RI{slash}CLK-Pad1)") (class "Default")
      (node (ref "U4") (pin "1") (pinfunction "RI/CLK_1") (pintype "unspecified+no_connect"))
    )
    (net (code "72") (name "unconnected-(U4-RSTb-Pad9)") (class "Default")
      (node (ref "U4") (pin "9") (pinfunction "RSTb_9") (pintype "unspecified+no_connect"))
    )
    (net (code "73") (name "unconnected-(U4-SUSPEND-Pad17)") (class "Default")
      (node (ref "U4") (pin "17") (pinfunction "SUSPEND_17") (pintype "unspecified+no_connect"))
    )
    (net (code "74") (name "unconnected-(U4-SUSPENDb-Pad15)") (class "Default")
      (node (ref "U4") (pin "15") (pinfunction "SUSPENDb_15") (pintype "unspecified+no_connect"))
    )
    (net (code "75") (name "unconnected-(U5-NC-Pad3)") (class "Default")
      (node (ref "U5") (pin "3") (pinfunction "NC_3") (pintype "unspecified+no_connect"))
    )
    (net (code "76") (name "unconnected-(USB1-SBU1-PadA8)") (class "Default")
      (node (ref "USB1") (pin "A8") (pinfunction "SBU1_A8") (pintype "unspecified+no_connect"))
    )
    (net (code "77") (name "unconnected-(USB1-SBU2-PadB8)") (class "Default")
      (node (ref "USB1") (pin "B8") (pinfunction "SBU2_B8") (pintype "unspecified+no_connect"))
    )
  )
)
